# Microcontroller.net
KiCad netlist of a schematic drawn in Altium Designer
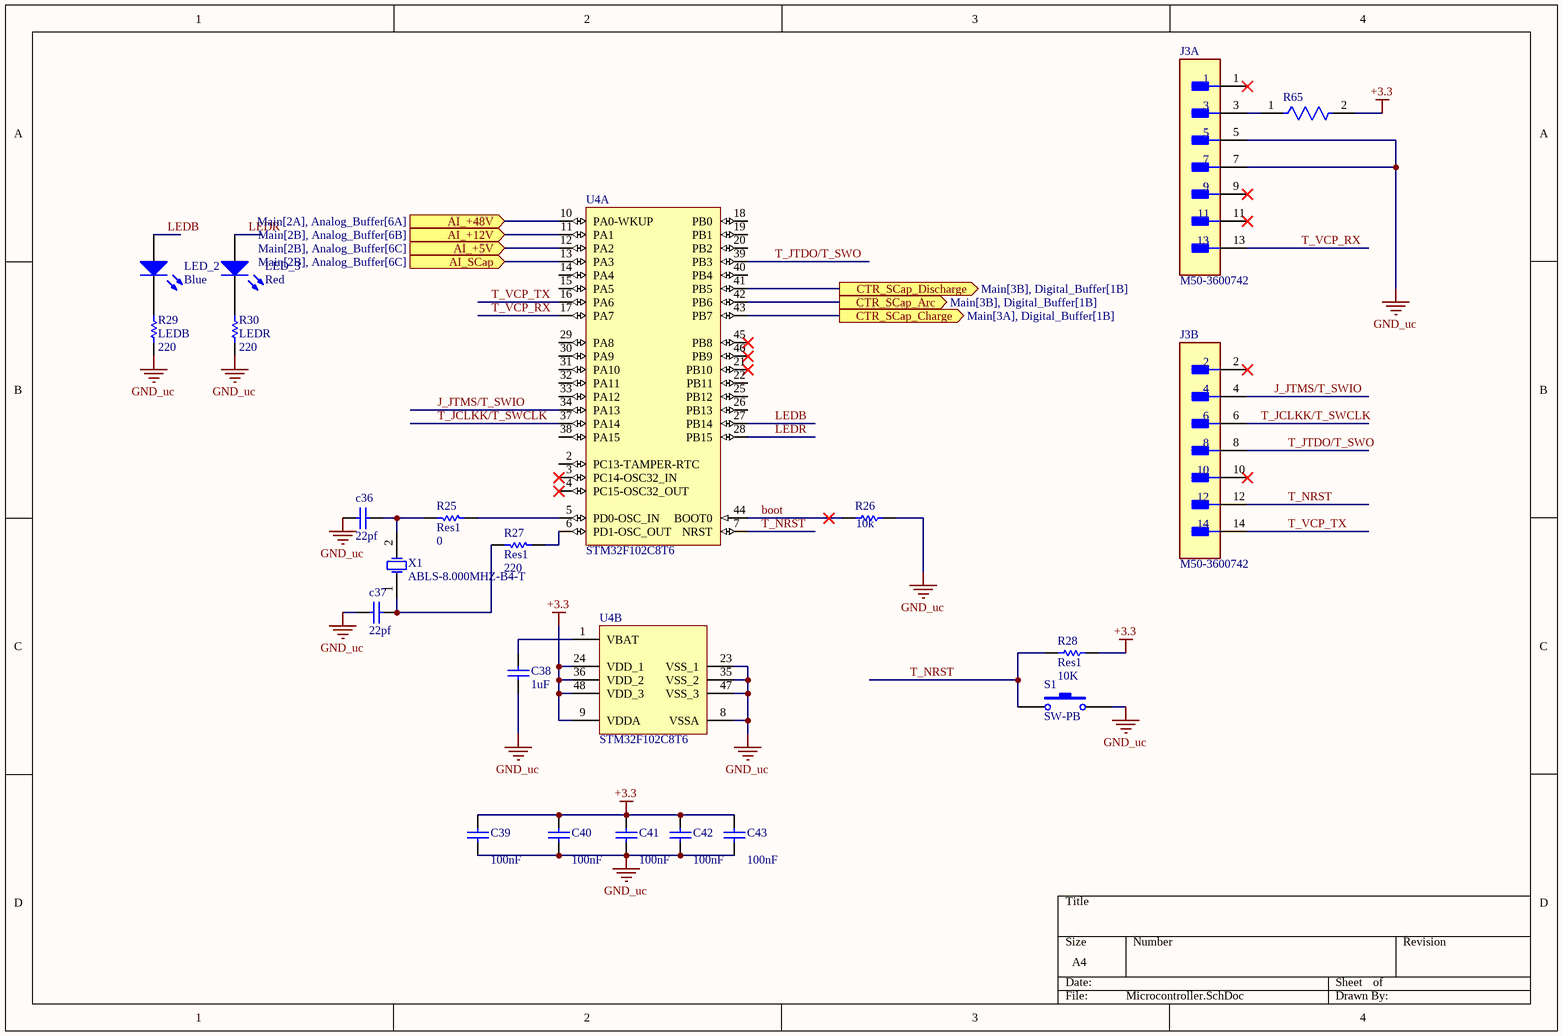
[diagram p0: Microcontroller.SchDoc]

(export (version "E")
  (design (tool "Eeschema 10.0.6"))
  (components
    (comp (ref "c36")
      (value "22pf")
      (footprint "0805C")
      (description "Capacitor")
      (fields (field (name "PUBLISHER") "Altium Limited"))
      (libsource (lib "KN2CLib") (part "Cap_UP"))
    )
    (comp (ref "c37")
      (value "22pf")
      (footprint "0805C")
      (description "Capacitor")
      (fields (field (name "PUBLISHER") "Altium Limited"))
      (libsource (lib "KN2CLib") (part "Cap_UP"))
    )
    (comp (ref "C38")
      (value "1uF")
      (footprint "0805C")
      (description "Capacitor")
      (fields (field (name "PUBLISHER") "Altium Limited"))
      (libsource (lib "KN2CLib") (part "Cap_UP"))
    )
    (comp (ref "C39")
      (value "100nF")
      (footprint "0805C")
      (description "Capacitor")
      (fields
        (field (name "MANUFACTURER") "Generic Components")
        (field (name "PUBLISHER") "Altium Hobart Technology Centre")
      )
      (libsource (lib "Miscellaneous Devices") (part "Cap"))
    )
    (comp (ref "C40")
      (value "100nF")
      (footprint "0805C")
      (description "Capacitor")
      (fields
        (field (name "MANUFACTURER") "Generic Components")
        (field (name "PUBLISHER") "Altium Hobart Technology Centre")
      )
      (libsource (lib "Miscellaneous Devices") (part "Cap"))
    )
    (comp (ref "C41")
      (value "100nF")
      (footprint "0805C")
      (description "Capacitor")
      (fields
        (field (name "MANUFACTURER") "Generic Components")
        (field (name "PUBLISHER") "Altium Hobart Technology Centre")
      )
      (libsource (lib "Miscellaneous Devices") (part "Cap"))
    )
    (comp (ref "C42")
      (value "100nF")
      (footprint "0805C")
      (description "Capacitor")
      (fields
        (field (name "MANUFACTURER") "Generic Components")
        (field (name "PUBLISHER") "Altium Hobart Technology Centre")
      )
      (libsource (lib "Miscellaneous Devices") (part "Cap"))
    )
    (comp (ref "C43")
      (value "100nF")
      (footprint "0805C")
      (description "Capacitor")
      (fields
        (field (name "MANUFACTURER") "Generic Components")
        (field (name "PUBLISHER") "Altium Hobart Technology Centre")
      )
      (libsource (lib "Miscellaneous Devices") (part "Cap"))
    )
    (comp (ref "J3")
      (value "M50-3600742")
      (footprint "FP-M50-3600742-MFG")
      (description "CONN HEADER SMD 14POS 1.27MM")
      (libsource (lib "Altium Content Vault") (part "7644e1a88aa4da17242a9b8d8257442"))
    )
    (comp (ref "LED_2")
      (value "Blue")
      (footprint "0805LED")
      (description "Typical BLUE SiC LED")
      (fields (field (name "PUBLISHER") "Altium Limited"))
      (libsource (lib "Miscellaneous Devices") (part "LED3"))
    )
    (comp (ref "LED_3")
      (value "Red")
      (footprint "0805LED")
      (description "Typical BLUE SiC LED")
      (fields (field (name "PUBLISHER") "Altium Limited"))
      (libsource (lib "Miscellaneous Devices") (part "LED3"))
    )
    (comp (ref "R25")
      (value "Res1")
      (footprint "0805L")
      (description "Resistor")
      (fields (field (name "ALTIUM_VALUE") "0") (field (name "PUBLISHER") "Altium Limited"))
      (libsource (lib "Miscellaneous Devices") (part "Res1"))
    )
    (comp (ref "R26")
      (value "10k")
      (footprint "0805L")
      (description "Resistor")
      (fields (field (name "Comment") "Res1") (field (name "PUBLISHER") "Altium Limited"))
      (libsource (lib "Miscellaneous Devices") (part "Res1"))
    )
    (comp (ref "R27")
      (value "Res1")
      (footprint "0805L")
      (description "Resistor")
      (fields (field (name "ALTIUM_VALUE") "220") (field (name "PUBLISHER") "Altium Limited"))
      (libsource (lib "Miscellaneous Devices") (part "Res1"))
    )
    (comp (ref "R28")
      (value "Res1")
      (footprint "0805L")
      (description "Resistor")
      (fields (field (name "ALTIUM_VALUE") "10K") (field (name "PUBLISHER") "Altium Limited"))
      (libsource (lib "Miscellaneous Devices") (part "Res1"))
    )
    (comp (ref "R29")
      (value "LEDB")
      (footprint "0805L")
      (description "Resistor")
      (fields (field (name "ALTIUM_VALUE") "220") (field (name "PUBLISHER") "Altium Limited"))
      (libsource (lib "Miscellaneous Devices") (part "Res1"))
    )
    (comp (ref "R30")
      (value "LEDR")
      (footprint "0805L")
      (description "Resistor")
      (fields (field (name "ALTIUM_VALUE") "220") (field (name "PUBLISHER") "Altium Limited"))
      (libsource (lib "Miscellaneous Devices") (part "Res1"))
    )
    (comp (ref "R65")
      (value "RC1206JR-070RL")
      (footprint "FP-RC1206-MFG")
      (description "RES SMD 0 OHM JUMPER 1/4W 1206")
      (fields
        (field (name "MANUFACTURER") "YAGEO")
        (field (name "OCTOPART") "https://octopart.com/rc1206jr-070rl-yageo-40025601")
      )
      (libsource (lib "Altium Content Vault") (part "1029c3af85768c4190bb7ad29bc67b5"))
    )
    (comp (ref "S1")
      (value "SW-PB")
      (footprint "sw-pb-4p")
      (description "Switch")
      (fields (field (name "PUBLISHER") "Altium Limited"))
      (libsource (lib "Miscellaneous Devices") (part "SW-PB"))
    )
    (comp (ref "U4")
      (value "STM32F102C8T6")
      (footprint "STM-LQFP48_N")
      (libsource (lib "STMicroelectronics STM32 F1") (part "STM32F102C8T6"))
    )
    (comp (ref "X1")
      (value "ABLS-8.000MHZ-B4-T")
      (footprint "ABRA-ABLS-14.7456MHZ-B2-T_V")
      (description "Low Profile Crystal, 8.0 MHz, +/- 30 ppm, -20 to 70 degC, 2-Pin SMD, RoHS, Tape and Reel")
      (fields (field (name "MANUFACTURER") "ABRACON") (field (name "TOLERANCE") "30PPM"))
      (libsource (lib "Altium Content Vault") (part "XTAL_1-2-2"))
    )
  )
  (nets
    (net (code "1") (name "+3.3") (class "Default")
      (node (ref "C39") (pin "2") (pinfunction "2_2") (pintype "passive"))
      (node (ref "C40") (pin "2") (pinfunction "2_2") (pintype "passive"))
      (node (ref "C41") (pin "2") (pinfunction "2_2") (pintype "passive"))
      (node (ref "C42") (pin "2") (pinfunction "2_2") (pintype "passive"))
      (node (ref "C43") (pin "2") (pinfunction "2_2") (pintype "passive"))
      (node (ref "R28") (pin "1") (pinfunction "1_1") (pintype "passive"))
      (node (ref "R65") (pin "2") (pinfunction "2_2") (pintype "passive"))
      (node (ref "U4") (pin "24") (pinfunction "VDD_1_24") (pintype "power_in"))
      (node (ref "U4") (pin "36") (pinfunction "VDD_2_36") (pintype "power_in"))
      (node (ref "U4") (pin "48") (pinfunction "VDD_3_48") (pintype "power_in"))
      (node (ref "U4") (pin "9") (pinfunction "VDDA_9") (pintype "power_in"))
    )
    (net (code "2") (name "/AI_+5V") (class "Default")
      (node (ref "U4") (pin "12") (pinfunction "PA2_12") (pintype "bidirectional"))
    )
    (net (code "3") (name "/AI_+12V") (class "Default")
      (node (ref "U4") (pin "11") (pinfunction "PA1_11") (pintype "bidirectional"))
    )
    (net (code "4") (name "/AI_+48V") (class "Default")
      (node (ref "U4") (pin "10") (pinfunction "PA0-WKUP_10") (pintype "bidirectional"))
    )
    (net (code "5") (name "/AI_SCap") (class "Default")
      (node (ref "U4") (pin "13") (pinfunction "PA3_13") (pintype "bidirectional"))
    )
    (net (code "6") (name "/CTR_SCap_Arc") (class "Default")
      (node (ref "U4") (pin "42") (pinfunction "PB6_42") (pintype "bidirectional"))
    )
    (net (code "7") (name "/CTR_SCap_Charge") (class "Default")
      (node (ref "U4") (pin "43") (pinfunction "PB7_43") (pintype "bidirectional"))
    )
    (net (code "8") (name "/CTR_SCap_Discharge") (class "Default")
      (node (ref "U4") (pin "41") (pinfunction "PB5_41") (pintype "bidirectional"))
    )
    (net (code "9") (name "/J_JTMS{slash}T_SWIO") (class "Default")
      (node (ref "J3") (pin "4") (pinfunction "4_4") (pintype "passive"))
      (node (ref "U4") (pin "34") (pinfunction "PA13_34") (pintype "bidirectional"))
    )
    (net (code "10") (name "/LEDB") (class "Default")
      (node (ref "LED_2") (pin "1") (pinfunction "A_1") (pintype "passive"))
      (node (ref "U4") (pin "27") (pinfunction "PB14_27") (pintype "bidirectional"))
    )
    (net (code "11") (name "/LEDR") (class "Default")
      (node (ref "LED_3") (pin "1") (pinfunction "A_1") (pintype "passive"))
      (node (ref "U4") (pin "28") (pinfunction "PB15_28") (pintype "bidirectional"))
    )
    (net (code "12") (name "/T_JCLKK{slash}T_SWCLK") (class "Default")
      (node (ref "J3") (pin "6") (pinfunction "6_6") (pintype "passive"))
      (node (ref "U4") (pin "37") (pinfunction "PA14_37") (pintype "bidirectional"))
    )
    (net (code "13") (name "/T_JTDO{slash}T_SWO") (class "Default")
      (node (ref "J3") (pin "8") (pinfunction "8_8") (pintype "passive"))
      (node (ref "U4") (pin "39") (pinfunction "PB3_39") (pintype "bidirectional"))
    )
    (net (code "14") (name "/T_NRST") (class "Default")
      (node (ref "J3") (pin "12") (pinfunction "12_12") (pintype "passive"))
      (node (ref "R28") (pin "2") (pinfunction "2_2") (pintype "passive"))
      (node (ref "S1") (pin "1") (pinfunction "1_1") (pintype "passive"))
      (node (ref "U4") (pin "7") (pinfunction "NRST_7") (pintype "bidirectional"))
    )
    (net (code "15") (name "/T_VCP_RX") (class "Default")
      (node (ref "J3") (pin "13") (pinfunction "13_13") (pintype "passive"))
      (node (ref "U4") (pin "17") (pinfunction "PA7_17") (pintype "bidirectional"))
    )
    (net (code "16") (name "/T_VCP_TX") (class "Default")
      (node (ref "J3") (pin "14") (pinfunction "14_14") (pintype "passive"))
      (node (ref "U4") (pin "16") (pinfunction "PA6_16") (pintype "bidirectional"))
    )
    (net (code "17") (name "/boot") (class "Default")
      (node (ref "R26") (pin "1") (pinfunction "1_1") (pintype "passive"))
      (node (ref "U4") (pin "44") (pinfunction "BOOT0_44") (pintype "input"))
    )
    (net (code "18") (name "GND_uc") (class "Default")
      (node (ref "C38") (pin "1") (pinfunction "1_1") (pintype "passive"))
      (node (ref "C39") (pin "1") (pinfunction "1_1") (pintype "passive"))
      (node (ref "C40") (pin "1") (pinfunction "1_1") (pintype "passive"))
      (node (ref "C41") (pin "1") (pinfunction "1_1") (pintype "passive"))
      (node (ref "C42") (pin "1") (pinfunction "1_1") (pintype "passive"))
      (node (ref "C43") (pin "1") (pinfunction "1_1") (pintype "passive"))
      (node (ref "J3") (pin "5") (pinfunction "5_5") (pintype "passive"))
      (node (ref "J3") (pin "7") (pinfunction "7_7") (pintype "passive"))
      (node (ref "R26") (pin "2") (pinfunction "2_2") (pintype "passive"))
      (node (ref "R29") (pin "2") (pinfunction "2_2") (pintype "passive"))
      (node (ref "R30") (pin "1") (pinfunction "1_1") (pintype "passive"))
      (node (ref "S1") (pin "2") (pinfunction "2_2") (pintype "passive"))
      (node (ref "U4") (pin "23") (pinfunction "VSS_1_23") (pintype "power_in"))
      (node (ref "U4") (pin "35") (pinfunction "VSS_2_35") (pintype "power_in"))
      (node (ref "U4") (pin "47") (pinfunction "VSS_3_47") (pintype "power_in"))
      (node (ref "U4") (pin "8") (pinfunction "VSSA_8") (pintype "power_in"))
      (node (ref "c36") (pin "2") (pinfunction "2_2") (pintype "passive"))
      (node (ref "c37") (pin "2") (pinfunction "2_2") (pintype "passive"))
    )
    (net (code "19") (name "Net-(J3-Pad3)") (class "Default")
      (node (ref "J3") (pin "3") (pinfunction "3_3") (pintype "passive"))
      (node (ref "R65") (pin "1") (pinfunction "1_1") (pintype "passive"))
    )
    (net (code "20") (name "Net-(LED_2-K)") (class "Default")
      (node (ref "LED_2") (pin "2") (pinfunction "K_2") (pintype "passive"))
      (node (ref "R29") (pin "1") (pinfunction "1_1") (pintype "passive"))
    )
    (net (code "21") (name "Net-(LED_3-K)") (class "Default")
      (node (ref "LED_3") (pin "2") (pinfunction "K_2") (pintype "passive"))
      (node (ref "R30") (pin "2") (pinfunction "2_2") (pintype "passive"))
    )
    (net (code "22") (name "Net-(U4A-PD0-OSC_IN)") (class "Default")
      (node (ref "R25") (pin "1") (pinfunction "1_1") (pintype "passive"))
      (node (ref "U4") (pin "5") (pinfunction "PD0-OSC_IN_5") (pintype "bidirectional"))
    )
    (net (code "23") (name "Net-(U4A-PD1-OSC_OUT)") (class "Default")
      (node (ref "R27") (pin "2") (pinfunction "2_2") (pintype "passive"))
      (node (ref "U4") (pin "6") (pinfunction "PD1-OSC_OUT_6") (pintype "bidirectional"))
    )
    (net (code "24") (name "Net-(U4B-VBAT)") (class "Default")
      (node (ref "C38") (pin "2") (pinfunction "2_2") (pintype "passive"))
      (node (ref "U4") (pin "1") (pinfunction "VBAT_1") (pintype "power_in"))
    )
    (net (code "25") (name "Net-(X1-X1)") (class "Default")
      (node (ref "R27") (pin "1") (pinfunction "1_1") (pintype "passive"))
      (node (ref "X1") (pin "1") (pinfunction "X1_1") (pintype "passive"))
      (node (ref "c37") (pin "1") (pinfunction "1_1") (pintype "passive"))
    )
    (net (code "26") (name "Net-(X1-X2)") (class "Default")
      (node (ref "R25") (pin "2") (pinfunction "2_2") (pintype "passive"))
      (node (ref "X1") (pin "2") (pinfunction "X2_2") (pintype "passive"))
      (node (ref "c36") (pin "1") (pinfunction "1_1") (pintype "passive"))
    )
    (net (code "27") (name "unconnected-(J3-Pad1)") (class "Default")
      (node (ref "J3") (pin "1") (pinfunction "1_1") (pintype "passive+no_connect"))
    )
    (net (code "28") (name "unconnected-(J3-Pad2)") (class "Default")
      (node (ref "J3") (pin "2") (pinfunction "2_2") (pintype "passive+no_connect"))
    )
    (net (code "29") (name "unconnected-(J3-Pad9)") (class "Default")
      (node (ref "J3") (pin "9") (pinfunction "9_9") (pintype "passive+no_connect"))
    )
    (net (code "30") (name "unconnected-(J3-Pad10)") (class "Default")
      (node (ref "J3") (pin "10") (pinfunction "10_10") (pintype "passive+no_connect"))
    )
    (net (code "31") (name "unconnected-(J3-Pad11)") (class "Default")
      (node (ref "J3") (pin "11") (pinfunction "11_11") (pintype "passive+no_connect"))
    )
    (net (code "32") (name "unconnected-(U4A-PA4-Pad14)") (class "Default")
      (node (ref "U4") (pin "14") (pinfunction "PA4_14") (pintype "bidirectional"))
    )
    (net (code "33") (name "unconnected-(U4A-PA5-Pad15)") (class "Default")
      (node (ref "U4") (pin "15") (pinfunction "PA5_15") (pintype "bidirectional"))
    )
    (net (code "34") (name "unconnected-(U4A-PA8-Pad29)") (class "Default")
      (node (ref "U4") (pin "29") (pinfunction "PA8_29") (pintype "bidirectional"))
    )
    (net (code "35") (name "unconnected-(U4A-PA9-Pad30)") (class "Default")
      (node (ref "U4") (pin "30") (pinfunction "PA9_30") (pintype "bidirectional"))
    )
    (net (code "36") (name "unconnected-(U4A-PA10-Pad31)") (class "Default")
      (node (ref "U4") (pin "31") (pinfunction "PA10_31") (pintype "bidirectional"))
    )
    (net (code "37") (name "unconnected-(U4A-PA11-Pad32)") (class "Default")
      (node (ref "U4") (pin "32") (pinfunction "PA11_32") (pintype "bidirectional"))
    )
    (net (code "38") (name "unconnected-(U4A-PA12-Pad33)") (class "Default")
      (node (ref "U4") (pin "33") (pinfunction "PA12_33") (pintype "bidirectional"))
    )
    (net (code "39") (name "unconnected-(U4A-PA15-Pad38)") (class "Default")
      (node (ref "U4") (pin "38") (pinfunction "PA15_38") (pintype "bidirectional"))
    )
    (net (code "40") (name "unconnected-(U4A-PB0-Pad18)") (class "Default")
      (node (ref "U4") (pin "18") (pinfunction "PB0_18") (pintype "bidirectional"))
    )
    (net (code "41") (name "unconnected-(U4A-PB1-Pad19)") (class "Default")
      (node (ref "U4") (pin "19") (pinfunction "PB1_19") (pintype "bidirectional"))
    )
    (net (code "42") (name "unconnected-(U4A-PB2-Pad20)") (class "Default")
      (node (ref "U4") (pin "20") (pinfunction "PB2_20") (pintype "bidirectional"))
    )
    (net (code "43") (name "unconnected-(U4A-PB4-Pad40)") (class "Default")
      (node (ref "U4") (pin "40") (pinfunction "PB4_40") (pintype "bidirectional"))
    )
    (net (code "44") (name "unconnected-(U4A-PB8-Pad45)") (class "Default")
      (node (ref "U4") (pin "45") (pinfunction "PB8_45") (pintype "bidirectional+no_connect"))
    )
    (net (code "45") (name "unconnected-(U4A-PB9-Pad46)") (class "Default")
      (node (ref "U4") (pin "46") (pinfunction "PB9_46") (pintype "bidirectional+no_connect"))
    )
    (net (code "46") (name "unconnected-(U4A-PB10-Pad21)") (class "Default")
      (node (ref "U4") (pin "21") (pinfunction "PB10_21") (pintype "bidirectional+no_connect"))
    )
    (net (code "47") (name "unconnected-(U4A-PB11-Pad22)") (class "Default")
      (node (ref "U4") (pin "22") (pinfunction "PB11_22") (pintype "bidirectional"))
    )
    (net (code "48") (name "unconnected-(U4A-PB12-Pad25)") (class "Default")
      (node (ref "U4") (pin "25") (pinfunction "PB12_25") (pintype "bidirectional"))
    )
    (net (code "49") (name "unconnected-(U4A-PB13-Pad26)") (class "Default")
      (node (ref "U4") (pin "26") (pinfunction "PB13_26") (pintype "bidirectional"))
    )
    (net (code "50") (name "unconnected-(U4A-PC13-TAMPER-RTC-Pad2)") (class "Default")
      (node (ref "U4") (pin "2") (pinfunction "PC13-TAMPER-RTC_2") (pintype "bidirectional"))
    )
    (net (code "51") (name "unconnected-(U4A-PC14-OSC32_IN-Pad3)") (class "Default")
      (node (ref "U4") (pin "3") (pinfunction "PC14-OSC32_IN_3") (pintype "bidirectional+no_connect"))
    )
    (net (code "52") (name "unconnected-(U4A-PC15-OSC32_OUT-Pad4)") (class "Default")
      (node (ref "U4") (pin "4") (pinfunction "PC15-OSC32_OUT_4") (pintype "bidirectional+no_connect"))
    )
  )
)
